# Luminode_Controller_Mark_II.net
KiCad netlist of a schematic drawn in EAGLE
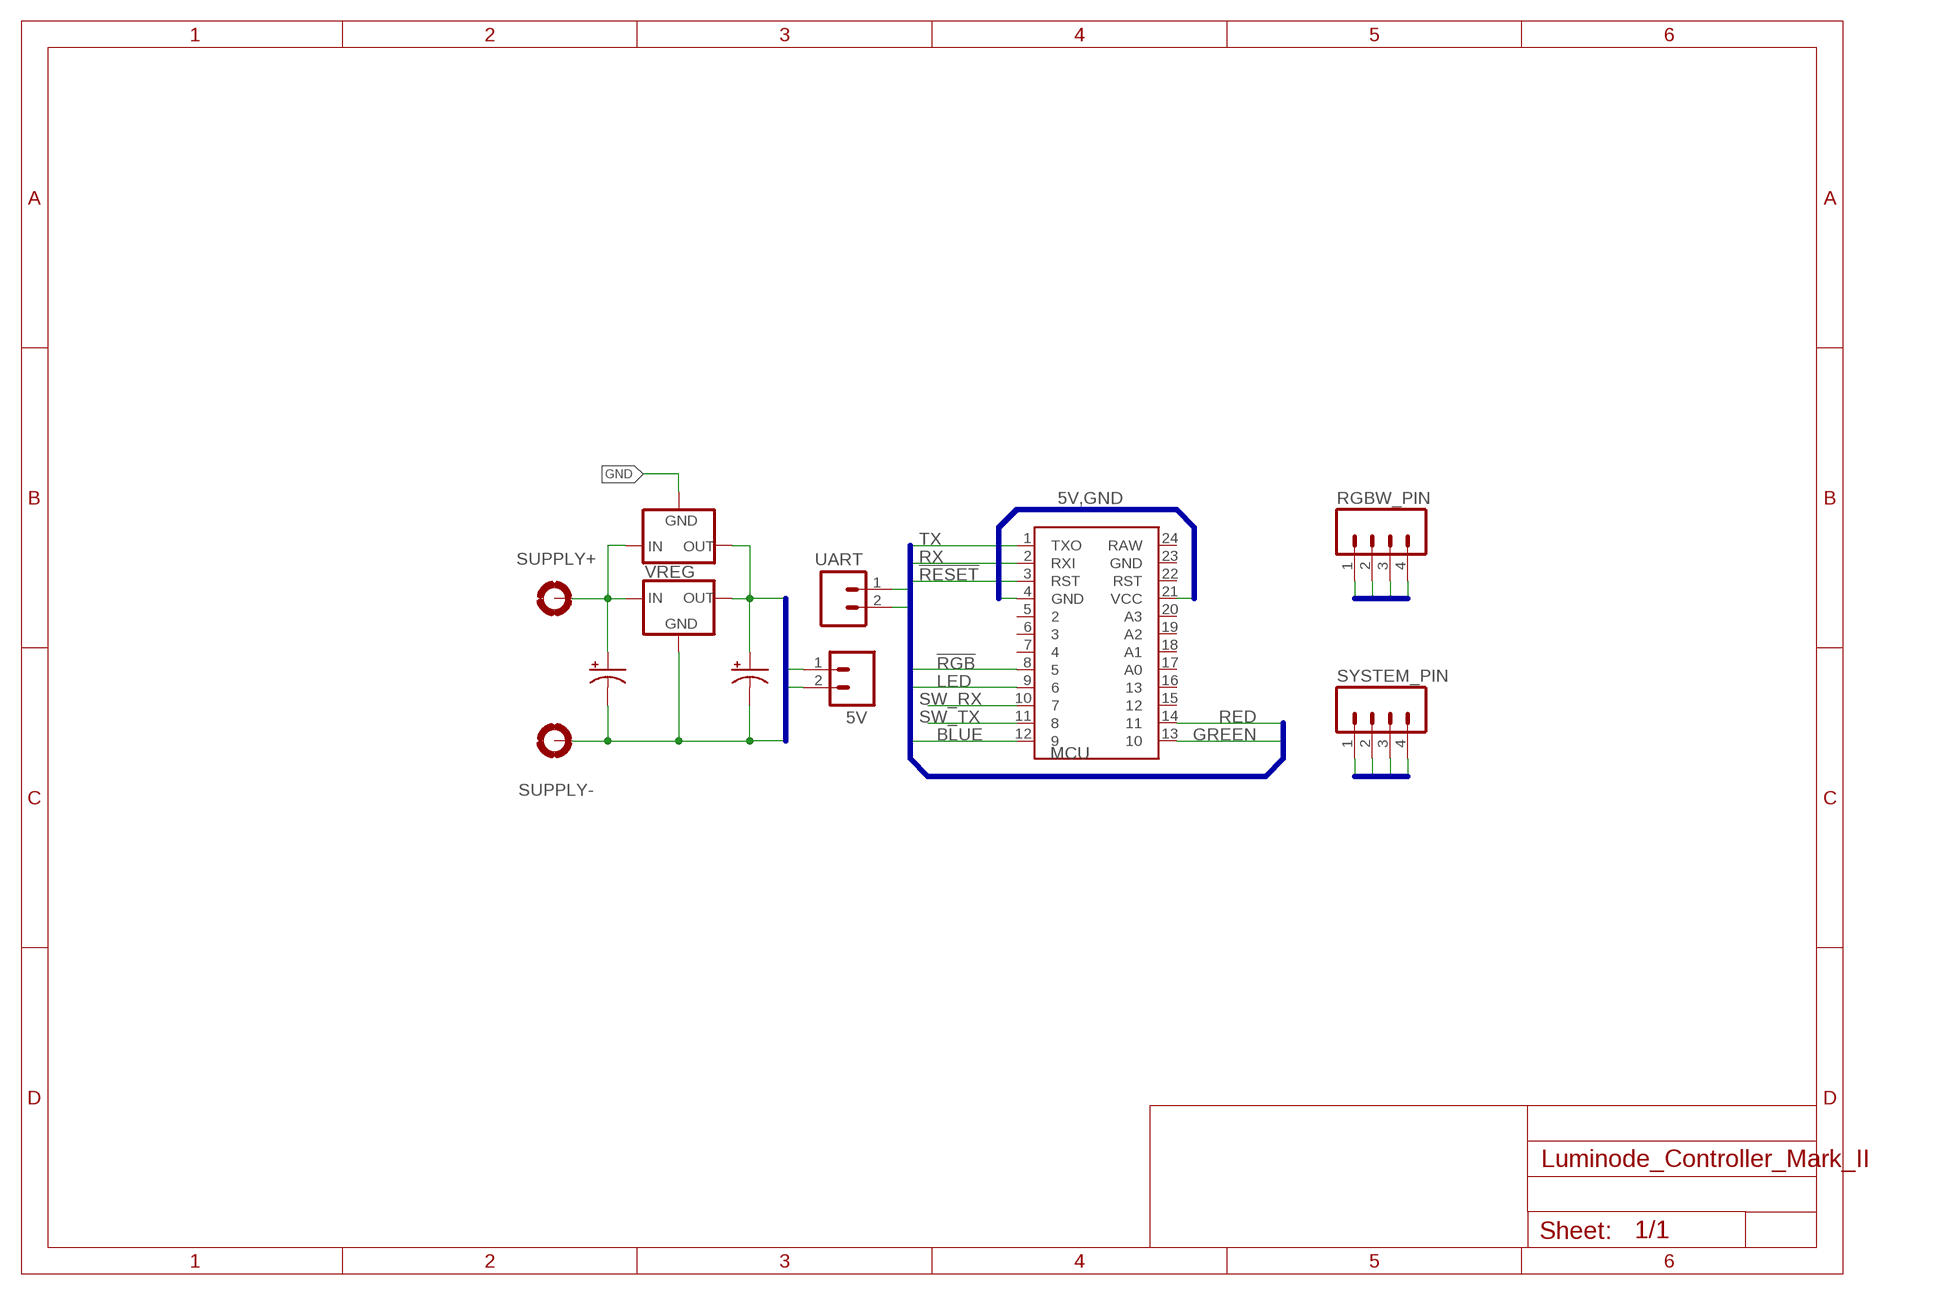
[diagram p0: schematic, sheet 1]

(export (version "E")
  (design (tool "Eeschema 10.0.6"))
  (components
    (comp (ref "5V")
      (value "M02PTH")
      (footprint "eagle-import:1X02")
      (libsource (lib "eagle-import") (part "M02PTH"))
    )
    (comp (ref "C_IN")
      (value "CPOL-USSMCB")
      (footprint "eagle-import:SMC_B")
      (libsource (lib "eagle-import") (part "CPOL-USSMCB"))
    )
    (comp (ref "C_OUT")
      (value "CPOL-USSMCB")
      (footprint "eagle-import:SMC_B")
      (libsource (lib "eagle-import") (part "CPOL-USSMCB"))
    )
    (comp (ref "MCU")
      (value "ARDUINO_MINI")
      (footprint "eagle-import:ARDUINO_MINI")
      (libsource (lib "eagle-import") (part "ARDUINO_MINI"))
    )
    (comp (ref "RGBW_PIN")
      (value "M04PTH")
      (footprint "eagle-import:1X04")
      (libsource (lib "eagle-import") (part "M04PTH"))
    )
    (comp (ref "SUPPLY+")
      (value "+V")
      (footprint "eagle-import:3,0-PAD")
      (libsource (lib "eagle-import") (part "MOUNT-PAD-ROUND3.0"))
    )
    (comp (ref "SUPPLY-")
      (value "-V")
      (footprint "eagle-import:3,0-PAD")
      (libsource (lib "eagle-import") (part "MOUNT-PAD-ROUND3.0"))
    )
    (comp (ref "SYSTEM_PIN")
      (value "M04PTH")
      (footprint "eagle-import:1X04")
      (libsource (lib "eagle-import") (part "M04PTH"))
    )
    (comp (ref "UART")
      (value "M02PTH")
      (footprint "eagle-import:1X02")
      (libsource (lib "eagle-import") (part "M02PTH"))
    )
    (comp (ref "VREG")
      (value "7805")
      (footprint "eagle-import:SOT223")
      (libsource (lib "eagle-import") (part "LM1117"))
    )
    (comp (ref "VREG_ALT")
      (value "V_REG_78XXSINK")
      (footprint "eagle-import:TO220-IGO")
      (libsource (lib "eagle-import") (part "V_REG_78XXSINK"))
    )
  )
  (nets
    (net (code "1") (name "/5V") (class "Default")
      (node (ref "5V") (pin "1") (pinfunction "1_1") (pintype "passive"))
      (node (ref "C_OUT") (pin "+") (pinfunction "+_+") (pintype "passive"))
      (node (ref "MCU") (pin "21") (pinfunction "VCC_21") (pintype "bidirectional"))
      (node (ref "SYSTEM_PIN") (pin "1") (pinfunction "1_1") (pintype "passive"))
      (node (ref "VREG") (pin "2") (pinfunction "OUT_2") (pintype "passive"))
      (node (ref "VREG_ALT") (pin "OUT") (pinfunction "OUT_OUT") (pintype "output"))
    )
    (net (code "2") (name "/BLUE") (class "Default")
      (node (ref "MCU") (pin "12") (pinfunction "9_12") (pintype "bidirectional"))
      (node (ref "RGBW_PIN") (pin "3") (pinfunction "3_3") (pintype "passive"))
    )
    (net (code "3") (name "/GREEN") (class "Default")
      (node (ref "MCU") (pin "13") (pinfunction "10_13") (pintype "bidirectional"))
      (node (ref "RGBW_PIN") (pin "2") (pinfunction "2_2") (pintype "passive"))
    )
    (net (code "4") (name "/LED") (class "Default")
      (node (ref "MCU") (pin "9") (pinfunction "6_9") (pintype "bidirectional"))
      (node (ref "RGBW_PIN") (pin "4") (pinfunction "4_4") (pintype "passive"))
    )
    (net (code "5") (name "/RED") (class "Default")
      (node (ref "MCU") (pin "14") (pinfunction "11_14") (pintype "bidirectional"))
      (node (ref "RGBW_PIN") (pin "1") (pinfunction "1_1") (pintype "passive"))
    )
    (net (code "6") (name "/RX") (class "Default")
      (node (ref "MCU") (pin "2") (pinfunction "RXI_2") (pintype "bidirectional"))
    )
    (net (code "7") (name "/SW_RX") (class "Default")
      (node (ref "MCU") (pin "10") (pinfunction "7_10") (pintype "bidirectional"))
      (node (ref "UART") (pin "2") (pinfunction "2_2") (pintype "passive"))
    )
    (net (code "8") (name "/SW_TX") (class "Default")
      (node (ref "MCU") (pin "11") (pinfunction "8_11") (pintype "bidirectional"))
      (node (ref "UART") (pin "1") (pinfunction "1_1") (pintype "passive"))
    )
    (net (code "9") (name "/TX") (class "Default")
      (node (ref "MCU") (pin "1") (pinfunction "TXO_1") (pintype "bidirectional"))
    )
    (net (code "10") (name "/VIN") (class "Default")
      (node (ref "C_IN") (pin "+") (pinfunction "+_+") (pintype "passive"))
      (node (ref "SUPPLY+") (pin "B3,0") (pinfunction "MOUNT_B3,0") (pintype "passive"))
      (node (ref "SYSTEM_PIN") (pin "2") (pinfunction "2_2") (pintype "passive"))
      (node (ref "VREG") (pin "3") (pinfunction "IN_3") (pintype "input"))
      (node (ref "VREG_ALT") (pin "IN") (pinfunction "IN_IN") (pintype "input"))
    )
    (net (code "12") (name "/~{RESET}") (class "Default")
      (node (ref "MCU") (pin "3") (pinfunction "RST_3") (pintype "bidirectional"))
    )
    (net (code "13") (name "/~{RGB}") (class "Default")
      (node (ref "MCU") (pin "8") (pinfunction "5_8") (pintype "bidirectional"))
      (node (ref "SYSTEM_PIN") (pin "4") (pinfunction "4_4") (pintype "passive"))
    )
    (net (code "14") (name "GND") (class "Default")
      (node (ref "5V") (pin "2") (pinfunction "2_2") (pintype "passive"))
      (node (ref "C_IN") (pin "-") (pinfunction "-_-") (pintype "passive"))
      (node (ref "C_OUT") (pin "-") (pinfunction "-_-") (pintype "passive"))
      (node (ref "MCU") (pin "4") (pinfunction "GND_4") (pintype "bidirectional"))
      (node (ref "SUPPLY-") (pin "B3,0") (pinfunction "MOUNT_B3,0") (pintype "passive"))
      (node (ref "SYSTEM_PIN") (pin "3") (pinfunction "3_3") (pintype "passive"))
      (node (ref "VREG") (pin "1") (pinfunction "GND_1") (pintype "input"))
      (node (ref "VREG_ALT") (pin "GND") (pinfunction "GND_GND") (pintype "input"))
    )
    (net (code "15") (name "unconnected-(MCU-2-Pad5)") (class "Default")
      (node (ref "MCU") (pin "5") (pinfunction "2_5") (pintype "bidirectional"))
    )
    (net (code "16") (name "unconnected-(MCU-3-Pad6)") (class "Default")
      (node (ref "MCU") (pin "6") (pinfunction "3_6") (pintype "bidirectional"))
    )
    (net (code "17") (name "unconnected-(MCU-4-Pad7)") (class "Default")
      (node (ref "MCU") (pin "7") (pinfunction "4_7") (pintype "bidirectional"))
    )
    (net (code "18") (name "unconnected-(MCU-12-Pad15)") (class "Default")
      (node (ref "MCU") (pin "15") (pinfunction "12_15") (pintype "bidirectional"))
    )
    (net (code "19") (name "unconnected-(MCU-13-Pad16)") (class "Default")
      (node (ref "MCU") (pin "16") (pinfunction "13_16") (pintype "bidirectional"))
    )
    (net (code "20") (name "unconnected-(MCU-A0-Pad17)") (class "Default")
      (node (ref "MCU") (pin "17") (pinfunction "A0_17") (pintype "bidirectional"))
    )
    (net (code "21") (name "unconnected-(MCU-A1-Pad18)") (class "Default")
      (node (ref "MCU") (pin "18") (pinfunction "A1_18") (pintype "bidirectional"))
    )
    (net (code "22") (name "unconnected-(MCU-A2-Pad19)") (class "Default")
      (node (ref "MCU") (pin "19") (pinfunction "A2_19") (pintype "bidirectional"))
    )
    (net (code "23") (name "unconnected-(MCU-A3-Pad20)") (class "Default")
      (node (ref "MCU") (pin "20") (pinfunction "A3_20") (pintype "bidirectional"))
    )
    (net (code "24") (name "unconnected-(MCU-GND-Pad23)") (class "Default")
      (node (ref "MCU") (pin "23") (pinfunction "GND_23") (pintype "bidirectional"))
    )
    (net (code "25") (name "unconnected-(MCU-RAW-Pad24)") (class "Default")
      (node (ref "MCU") (pin "24") (pinfunction "RAW_24") (pintype "bidirectional"))
    )
    (net (code "26") (name "unconnected-(MCU-RST-Pad22)") (class "Default")
      (node (ref "MCU") (pin "22") (pinfunction "RST_22") (pintype "bidirectional"))
    )
  )
)
